# first_designbr.net
KiCad netlist of a schematic drawn in EAGLE
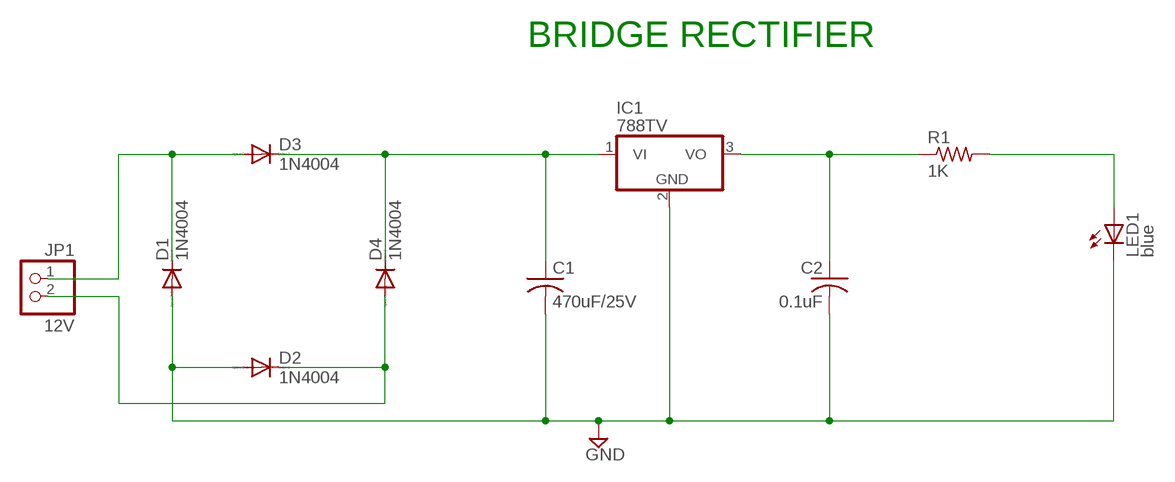
[diagram p0: schematic, sheet 1]

(export (version "E")
  (design (tool "Eeschema 10.0.6"))
  (components
    (comp (ref "C1")
      (value "470uF/25V")
      (footprint "eagle-import:C050-025X075")
      (libsource (lib "eagle-import") (part "C-US050-025X075"))
    )
    (comp (ref "C2")
      (value "0.1uF")
      (footprint "eagle-import:C025-024X044")
      (libsource (lib "eagle-import") (part "C-US025-024X044"))
    )
    (comp (ref "D1")
      (value "1N4004")
      (footprint "eagle-import:DO41-10")
      (libsource (lib "eagle-import") (part "1N4004"))
    )
    (comp (ref "D2")
      (value "1N4004")
      (footprint "eagle-import:DO41-10")
      (libsource (lib "eagle-import") (part "1N4004"))
    )
    (comp (ref "D3")
      (value "1N4004")
      (footprint "eagle-import:DO41-10")
      (libsource (lib "eagle-import") (part "1N4004"))
    )
    (comp (ref "D4")
      (value "1N4004")
      (footprint "eagle-import:DO41-10")
      (libsource (lib "eagle-import") (part "1N4004"))
    )
    (comp (ref "IC1")
      (value "788TV")
      (footprint "eagle-import:TO220V")
      (libsource (lib "eagle-import") (part "78TV8"))
    )
    (comp (ref "JP1")
      (value "12V")
      (footprint "eagle-import:1X02")
      (libsource (lib "eagle-import") (part "PINHD-1X2"))
    )
    (comp (ref "LED1")
      (value "blue")
      (footprint "eagle-import:LED5MM")
      (libsource (lib "eagle-import") (part "LED5MM"))
    )
    (comp (ref "R1")
      (value "1K")
      (footprint "eagle-import:0207_10")
      (libsource (lib "eagle-import") (part "R-US_0207/10"))
    )
  )
  (nets
    (net (code "1") (name "GND") (class "Default")
      (node (ref "C1") (pin "2") (pinfunction "2_2") (pintype "passive"))
      (node (ref "C2") (pin "2") (pinfunction "2_2") (pintype "passive"))
      (node (ref "D1") (pin "A") (pinfunction "A_A") (pintype "passive"))
      (node (ref "D2") (pin "A") (pinfunction "A_A") (pintype "passive"))
      (node (ref "IC1") (pin "2") (pinfunction "GND_2") (pintype "passive"))
      (node (ref "LED1") (pin "K") (pinfunction "C_K") (pintype "passive"))
    )
    (net (code "2") (name "Net-(D1-PadC)") (class "Default")
      (node (ref "D1") (pin "C") (pinfunction "C_C") (pintype "passive"))
      (node (ref "D3") (pin "A") (pinfunction "A_A") (pintype "passive"))
      (node (ref "JP1") (pin "1") (pinfunction "1_1") (pintype "passive"))
    )
    (net (code "3") (name "Net-(D2-PadC)") (class "Default")
      (node (ref "D2") (pin "C") (pinfunction "C_C") (pintype "passive"))
      (node (ref "D4") (pin "A") (pinfunction "A_A") (pintype "passive"))
      (node (ref "JP1") (pin "2") (pinfunction "2_2") (pintype "passive"))
    )
    (net (code "4") (name "Net-(IC1-VI)") (class "Default")
      (node (ref "C1") (pin "1") (pinfunction "1_1") (pintype "passive"))
      (node (ref "D3") (pin "C") (pinfunction "C_C") (pintype "passive"))
      (node (ref "D4") (pin "C") (pinfunction "C_C") (pintype "passive"))
      (node (ref "IC1") (pin "1") (pinfunction "VI_1") (pintype "input"))
    )
    (net (code "5") (name "Net-(IC1-VO)") (class "Default")
      (node (ref "C2") (pin "1") (pinfunction "1_1") (pintype "passive"))
      (node (ref "IC1") (pin "3") (pinfunction "VO_3") (pintype "passive"))
      (node (ref "R1") (pin "1") (pinfunction "1_1") (pintype "passive"))
    )
    (net (code "6") (name "Net-(LED1-PadA)") (class "Default")
      (node (ref "LED1") (pin "A") (pinfunction "A_A") (pintype "passive"))
      (node (ref "R1") (pin "2") (pinfunction "2_2") (pintype "passive"))
    )
  )
)
